# Power.net
KiCad netlist of a schematic drawn in Altium Designer
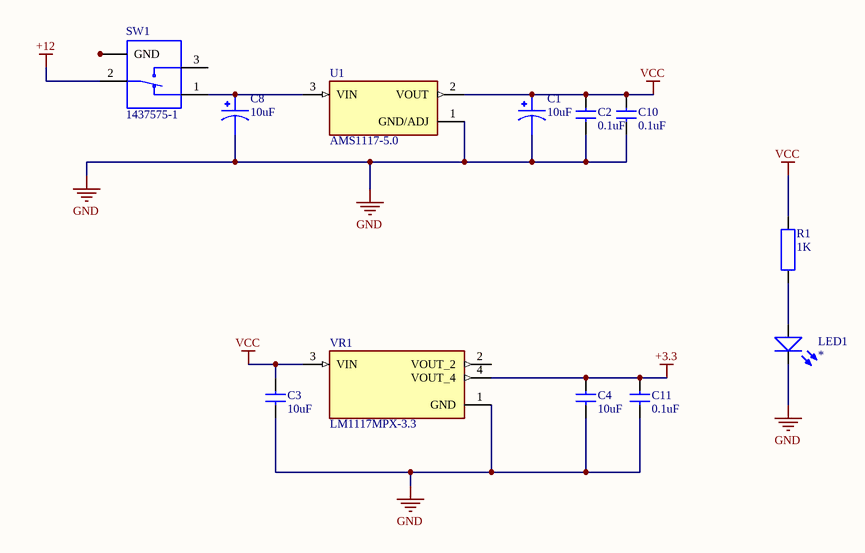
[diagram p0: Power.SchDoc]

(export (version "E")
  (design (tool "Eeschema 10.0.6"))
  (components
    (comp (ref "C1")
      (value "10uF")
      (footprint "CAPM3216X180")
      (description "10 ÂµF Molded Tantalum Capacitors 10 V 1206 (3216 Metric) 3Ohm")
      (fields (field (name "MP") "F971A106KAA") (field (name "MF") "AVX"))
      (libsource (lib "F971A106KAA") (part "F971A106KAA"))
    )
    (comp (ref "C2")
      (value "0.1uF")
      (footprint "SMD_CAPACITOR_0805")
      (description "Capacitor")
      (libsource (lib "VPP_Library") (part "Capacitor"))
    )
    (comp (ref "C3")
      (value "10uF")
      (footprint "SMD_CAPACITOR_0805")
      (description "Capacitor")
      (libsource (lib "VPP_Library") (part "Capacitor"))
    )
    (comp (ref "C4")
      (value "10uF")
      (footprint "SMD_CAPACITOR_0805")
      (description "Capacitor")
      (libsource (lib "VPP_Library") (part "Capacitor"))
    )
    (comp (ref "C8")
      (value "10uF")
      (footprint "CAPM3216X180")
      (description "10 ÂµF Molded Tantalum Capacitors 10 V 1206 (3216 Metric) 3Ohm")
      (fields (field (name "MP") "F971A106KAA") (field (name "MF") "AVX"))
      (libsource (lib "F971A106KAA") (part "F971A106KAA"))
    )
    (comp (ref "C10")
      (value "0.1uF")
      (footprint "SMD_CAPACITOR_0805")
      (description "Capacitor")
      (libsource (lib "VPP_Library") (part "Capacitor"))
    )
    (comp (ref "C11")
      (value "0.1uF")
      (footprint "SMD_CAPACITOR_0805")
      (description "Capacitor")
      (libsource (lib "VPP_Library") (part "Capacitor"))
    )
    (comp (ref "LED1")
      (value "*")
      (footprint "SMD_LED_0805")
      (description "LED")
      (fields (field (name "ALTIUM_VALUE") "*"))
      (libsource (lib "VPP_Library") (part "LED"))
    )
    (comp (ref "R1")
      (value "1K")
      (footprint "SMD_RESISTOR_0805")
      (description "Resistor")
      (libsource (lib "VPP_Library") (part "Resistor"))
    )
    (comp (ref "SW1")
      (value "1437575-1")
      (footprint "SW_MLL1200S")
      (description "Slide Switch 4PDT Through Hole, Right Angle")
      (fields (field (name "MF") "TE Connectivity"))
      (libsource (lib "1437575-1") (part "1437575-1"))
    )
    (comp (ref "U1")
      (value "AMS1117-5.0")
      (footprint "SOT229P700X180-4N")
      (description "1A LOW DROPOUT VOLTAGE REGULATOR")
      (fields (field (name "MF") "ams"))
      (libsource (lib "AMS1117-5.0") (part "AMS1117-5.0"))
    )
    (comp (ref "VR1")
      (value "LM1117MPX-3.3")
      (footprint "VREG_LM1117MPX-3.3")
      (description "800-mA 15-V linear voltage regulator")
      (fields (field (name "MF") "Texas Instruments"))
      (libsource (lib "LM1117MPX-3.3 StepDown3.3V") (part "LM1117MPX-3.3"))
    )
  )
  (nets
    (net (code "1") (name "+3.3") (class "Default")
      (node (ref "C11") (pin "1") (pinfunction "1_1") (pintype "passive"))
      (node (ref "C4") (pin "1") (pinfunction "1_1") (pintype "passive"))
      (node (ref "VR1") (pin "4") (pinfunction "VOUT_4_4") (pintype "output"))
    )
    (net (code "2") (name "+12") (class "Default")
      (node (ref "SW1") (pin "2") (pinfunction "2_2") (pintype "passive"))
    )
    (net (code "3") (name "GND") (class "Default")
      (node (ref "C1") (pin "2") (pinfunction "2_2") (pintype "passive"))
      (node (ref "C10") (pin "2") (pinfunction "2_2") (pintype "passive"))
      (node (ref "C11") (pin "2") (pinfunction "2_2") (pintype "passive"))
      (node (ref "C2") (pin "2") (pinfunction "2_2") (pintype "passive"))
      (node (ref "C3") (pin "2") (pinfunction "2_2") (pintype "passive"))
      (node (ref "C4") (pin "2") (pinfunction "2_2") (pintype "passive"))
      (node (ref "C8") (pin "2") (pinfunction "2_2") (pintype "passive"))
      (node (ref "LED1") (pin "2") (pinfunction "2_2") (pintype "passive"))
      (node (ref "U1") (pin "1") (pinfunction "GND/ADJ_1") (pintype "power_in"))
      (node (ref "VR1") (pin "1") (pinfunction "GND_1") (pintype "power_in"))
    )
    (net (code "4") (name "Net-(LED1-Pad1)") (class "Default")
      (node (ref "LED1") (pin "1") (pinfunction "1_1") (pintype "passive"))
      (node (ref "R1") (pin "2") (pinfunction "2_2") (pintype "passive"))
    )
    (net (code "5") (name "Net-(SW1-GND-PadG1)") (class "Default")
      (node (ref "SW1") (pin "G1") (pinfunction "GND_G1") (pintype "power_in"))
      (node (ref "SW1") (pin "G2") (pinfunction "GND_G2") (pintype "power_in"))
      (node (ref "SW1") (pin "G3") (pinfunction "GND_G3") (pintype "power_in"))
      (node (ref "SW1") (pin "G4") (pinfunction "GND_G4") (pintype "power_in"))
    )
    (net (code "6") (name "Net-(U1-VIN)") (class "Default")
      (node (ref "C8") (pin "1") (pinfunction "1_1") (pintype "passive"))
      (node (ref "SW1") (pin "1") (pinfunction "1_1") (pintype "passive"))
      (node (ref "U1") (pin "3") (pinfunction "VIN_3") (pintype "input"))
    )
    (net (code "7") (name "VCC") (class "Default")
      (node (ref "C1") (pin "1") (pinfunction "1_1") (pintype "passive"))
      (node (ref "C10") (pin "1") (pinfunction "1_1") (pintype "passive"))
      (node (ref "C2") (pin "1") (pinfunction "1_1") (pintype "passive"))
      (node (ref "C3") (pin "1") (pinfunction "1_1") (pintype "passive"))
      (node (ref "R1") (pin "1") (pinfunction "1_1") (pintype "passive"))
      (node (ref "U1") (pin "2") (pinfunction "VOUT_2") (pintype "output"))
      (node (ref "VR1") (pin "3") (pinfunction "VIN_3") (pintype "input"))
    )
    (net (code "8") (name "unconnected-(SW1-Pad3)") (class "Default")
      (node (ref "SW1") (pin "3") (pinfunction "3_3") (pintype "passive"))
    )
    (net (code "9") (name "unconnected-(VR1-VOUT_2-Pad2)") (class "Default")
      (node (ref "VR1") (pin "2") (pinfunction "VOUT_2_2") (pintype "output"))
    )
  )
)
